# DC_Power_Regulation_-_Copy.net
KiCad netlist of a schematic drawn in Altium Designer
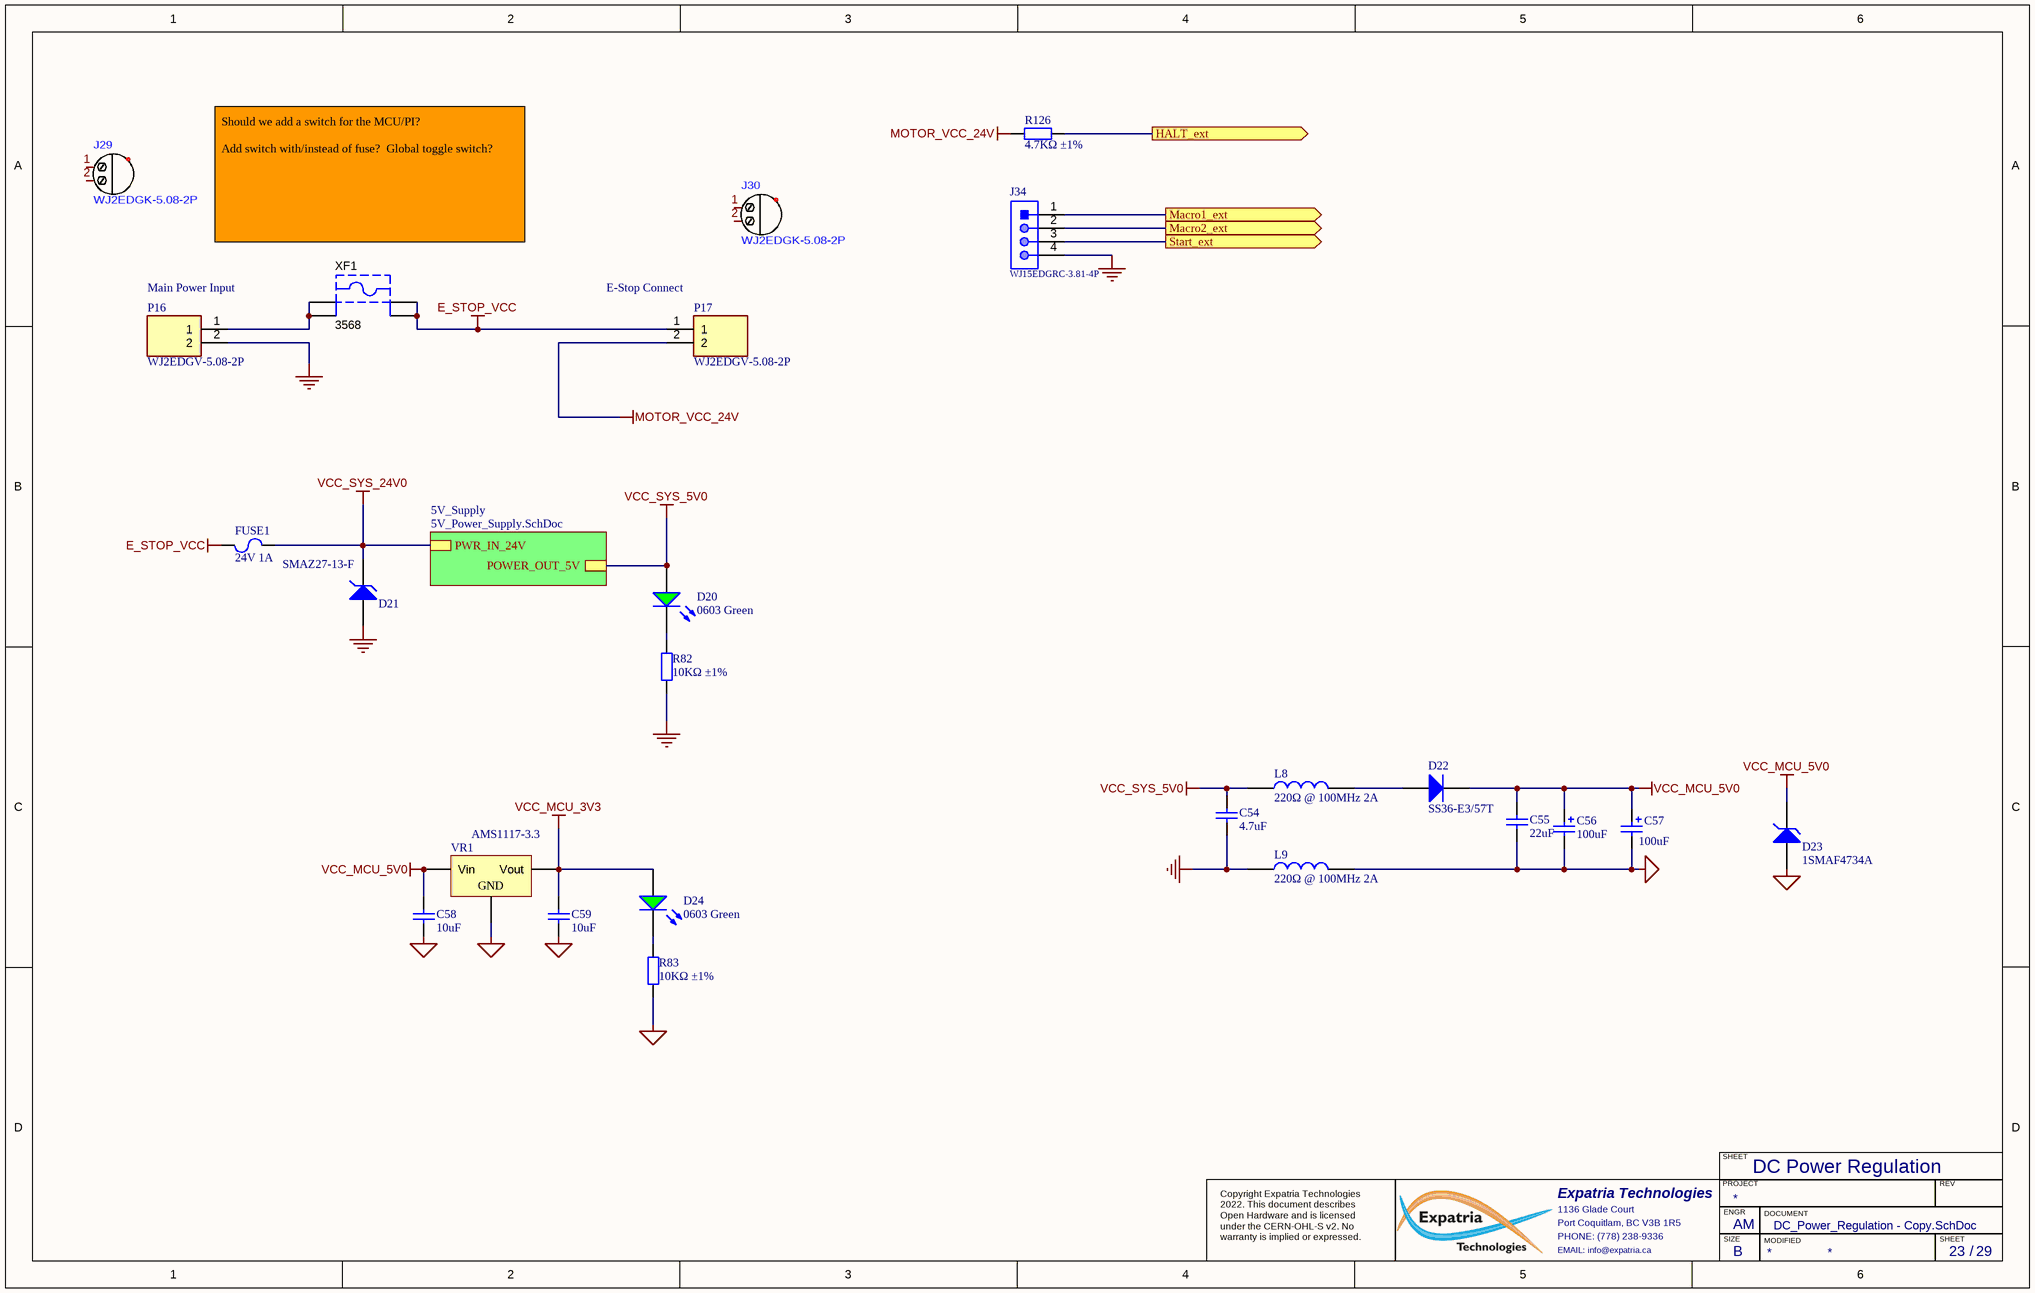
[diagram p0: DC_Power_Regulation - Copy.SchDoc]

(export (version "E")
  (design (tool "Eeschema 10.0.6"))
  (components
    (comp (ref "C54")
      (value "4.7uF")
      (footprint "0603_C")
      (description "Chip capacitors")
      (fields
        (field (name "MANUFACTURER") "Samsung Electro-Mechanics")
        (field (name "PARTNUMBER") "CL10A475KO8NNNC")
      )
      (libsource (lib "Cap") (part "0603 4.7uF (475) 10% 16V"))
    )
    (comp (ref "C55")
      (value "22uF")
      (footprint "0805_C")
      (description "Chip capacitors")
      (fields
        (field (name "MANUFACTURER") "Samsung Electro-Mechanics")
        (field (name "PARTNUMBER") "CL21A226MAQNNNE")
      )
      (libsource (lib "Cap") (part "0805 22uF (226) 20% 25V"))
    )
    (comp (ref "C56")
      (value "100uF")
      (footprint "CASE-B_3528")
      (description "Tantalum capacitor")
      (fields (field (name "MANUFACTURER") "AVX") (field (name "PARTNUMBER") "TAJB107K006RNJ"))
      (libsource (lib "Cap") (part "3528 100uF (107) 10% 6.3V"))
    )
    (comp (ref "C57")
      (value "100uF")
      (footprint "WCAP-ASLI_D6.3H7.7")
      (fields (field (name "MANUFACTURER") "Capxon International Elec"))
      (libsource (lib "IQAnalog") (part "865080445010"))
    )
    (comp (ref "C58")
      (value "10uF")
      (footprint "1206_C")
      (description "Chip capacitors")
      (fields
        (field (name "MANUFACTURER") "Samsung Electro-Mechanics")
        (field (name "PARTNUMBER") "CL31A106KBHNNNE")
      )
      (libsource (lib "Cap") (part "1206 10uF (106) 10% 50V"))
    )
    (comp (ref "C59")
      (value "10uF")
      (footprint "1206_C")
      (description "Chip capacitors")
      (fields
        (field (name "MANUFACTURER") "Samsung Electro-Mechanics")
        (field (name "PARTNUMBER") "CL31A106KBHNNNE")
      )
      (libsource (lib "Cap") (part "1206 10uF (106) 10% 50V"))
    )
    (comp (ref "D20")
      (value "0603 Green")
      (footprint "0603_LED_S1")
      (description "LED")
      (libsource (lib "LED") (part "0603 LED Green"))
    )
    (comp (ref "D21")
      (value "SMAZ27-13-F")
      (footprint "DIOM5226X240N")
      (description "27V ±5% 1W 500nA @ 20.5V SMA(DO-214AC) Zener Diodes RoHS")
      (libsource (lib "PrintNC_GRBLHAL_Breakout") (part "BZT52C27"))
    )
    (comp (ref "D22")
      (value "SS36-E3/57T")
      (footprint "SMC(DO-214AB)_S1")
      (description "DIODE SCHOTTKY 60V 3A DO214AB")
      (libsource (lib "Diode") (part "SMC(DO-214AB) SS36-E3/57T"))
    )
    (comp (ref "D23")
      (value "1SMAF4734A")
      (footprint "DIOM5226X240N")
      (description "27V ±5% 1W 500nA @ 20.5V SMA(DO-214AC) Zener Diodes RoHS")
      (libsource (lib "PrintNC_GRBLHAL_Breakout") (part "BZT52C27"))
    )
    (comp (ref "D24")
      (value "0603 Green")
      (footprint "0603_LED_S1")
      (description "LED")
      (libsource (lib "LED") (part "0603 LED Green"))
    )
    (comp (ref "FUSE1")
      (value "24V 1A")
      (footprint "1206_C")
      (description "24V 1A 0.1s 1206 PTC Resettable Fuses RoHS")
      (fields
        (field (name "MANUFACTURER") "Jinrui Electronic Materials Co.")
        (field (name "PARTNUMBER") "JK-nSMD050-24")
      )
      (libsource (lib "PrintNC_GRBLHAL_Breakout") (part "JK-nSMD050-24"))
    )
    (comp (ref "J29")
      (value "WJ2EDGK-5.08-2P")
      (description "5.08mm Green Plug P=5.08mm Pluggable System Terminal Block ROHS")
      (fields (field (name "MANUFACTURER") "Kangnex"))
      (libsource (lib "Sienci_Labs") (part "WJ2EDGK-5.08-2P"))
    )
    (comp (ref "J30")
      (value "WJ2EDGK-5.08-2P")
      (description "5.08mm Green Plug P=5.08mm Pluggable System Terminal Block ROHS")
      (fields (field (name "MANUFACTURER") "Kangnex"))
      (libsource (lib "Sienci_Labs") (part "WJ2EDGK-5.08-2P"))
    )
    (comp (ref "J34")
      (value "WJ15EDGRC-3.81-4P")
      (footprint "SHDRRA4W85P0X381_1X4_1612X915X720P")
      (description "3.81mm Green Board Edge/Receptacle-Close Push-Pull,P=3.81mm Pluggable System Terminal Block ROHS")
      (fields (field (name "MANUFACTURER") "Ningbo Kangnex Elec"))
      (libsource (lib "Sienci_Labs") (part "WJ15EDGRC-3.81-4P"))
    )
    (comp (ref "L8")
      (value "220Ω @ 100MHz 2A")
      (footprint "0805_C")
      (description "220Ω @ 100MHz 2A 150mΩ 0805 Ferrite Beads ROHS")
      (libsource (lib "FBEAD") (part "0402 220R@100Mhz 0.1A"))
    )
    (comp (ref "L9")
      (value "220Ω @ 100MHz 2A")
      (footprint "0805_C")
      (description "220Ω @ 100MHz 1 2A 150mΩ 0805 Ferrite Beads ROHS")
      (libsource (lib "FBEAD") (part "0402 220R@100Mhz 0.1A"))
    )
    (comp (ref "P16")
      (value "WJ2EDGV-5.08-2P")
      (footprint "WJ2EDGV5082P")
      (description "5.08mm Green Board Edge/Receptacle-Open Straight,P=5.08mm Pluggable System Terminal Block ROHS")
      (fields (field (name "MANUFACTURER") "Kangnex"))
      (libsource (lib "Sienci_Labs") (part "WJ2EDGV-5.08-2P"))
    )
    (comp (ref "P17")
      (value "WJ2EDGV-5.08-2P")
      (footprint "WJ2EDGV5082P")
      (description "5.08mm Green Board Edge/Receptacle-Open Straight,P=5.08mm Pluggable System Terminal Block ROHS")
      (fields (field (name "MANUFACTURER") "Kangnex"))
      (libsource (lib "") (part "WJ2EDGV-5.08-2P_1"))
    )
    (comp (ref "R82")
      (value "10KΩ ±1%")
      (footprint "0603_R")
      (description "Chip resistor")
      (fields (field (name "MANUFACTURER") "Uniroyal Elec") (field (name "PARTNUMBER") "0603WAF1002T5E"))
      (libsource (lib "RES") (part "0603 10K (1002) 1%"))
    )
    (comp (ref "R83")
      (value "10KΩ ±1%")
      (footprint "0603_R")
      (description "Chip resistor")
      (fields (field (name "MANUFACTURER") "Uniroyal Elec") (field (name "PARTNUMBER") "0603WAF1002T5E"))
      (libsource (lib "RES") (part "0603 10K (1002) 1%"))
    )
    (comp (ref "R126")
      (value "4.7KΩ ±1%")
      (footprint "0603_R")
      (description "Chip resistor")
      (fields (field (name "MANUFACTURER") "Uniroyal Elec") (field (name "PARTNUMBER") "0603WAF4701T5E"))
      (libsource (lib "Sienci_Labs") (part "0603 4.7K (4701) 1%"))
    )
    (comp (ref "VR1")
      (value "AMS1117-3.3")
      (footprint "SOT-223")
      (description "Vout=3.3V 1A 72dB@(120Hz) (LDO)")
      (fields (field (name "MANUFACTURER") "AMS"))
      (libsource (lib "LDO") (part "SOT-223 AMS1117-3.3"))
    )
    (comp (ref "XF1")
      (value "3568")
      (footprint "KSTN-3568_V")
      (description "Fuse Holder, 20 A, 500 V, -50 to 145 degC, 4-Pin THD, RoHS")
      (fields
        (field (name "MANUFACTURER") "Keystone Electronics")
        (field (name "MANUFACTURER PART NUMBER") "3568-20")
      )
      (libsource (lib "Sienci_Labs") (part "3568-20"))
    )
  )
  (nets
    (net (code "1") (name "/HALT_ext") (class "Default")
      (node (ref "R126") (pin "1") (pinfunction "1_1") (pintype "passive"))
    )
    (net (code "2") (name "/Macro1_ext") (class "Default")
      (node (ref "J34") (pin "1") (pinfunction "1_1") (pintype "passive"))
    )
    (net (code "3") (name "/Macro2_ext") (class "Default")
      (node (ref "J34") (pin "2") (pinfunction "2_2") (pintype "passive"))
    )
    (net (code "4") (name "/Start_ext") (class "Default")
      (node (ref "J34") (pin "3") (pinfunction "3_3") (pintype "passive"))
    )
    (net (code "5") (name "E_STOP_VCC") (class "Default")
      (node (ref "FUSE1") (pin "1") (pinfunction "1_1") (pintype "passive"))
      (node (ref "P17") (pin "1") (pinfunction "1_1") (pintype "passive"))
      (node (ref "XF1") (pin "3") (pinfunction "3_3") (pintype "passive"))
      (node (ref "XF1") (pin "4") (pinfunction "4_4") (pintype "passive"))
    )
    (net (code "6") (name "GND") (class "Default")
      (node (ref "C54") (pin "1") (pinfunction "1_1") (pintype "passive"))
      (node (ref "D21") (pin "1") (pinfunction "A_1") (pintype "passive"))
      (node (ref "J34") (pin "4") (pinfunction "4_4") (pintype "passive"))
      (node (ref "L9") (pin "1") (pinfunction "1_1") (pintype "passive"))
      (node (ref "P16") (pin "2") (pinfunction "2_2") (pintype "passive"))
      (node (ref "R82") (pin "1") (pinfunction "1_1") (pintype "passive"))
    )
    (net (code "7") (name "MCU_GND") (class "Default")
      (node (ref "C55") (pin "1") (pinfunction "1_1") (pintype "passive"))
      (node (ref "C56") (pin "2") (pinfunction "2_2") (pintype "passive"))
      (node (ref "C57") (pin "2") (pinfunction "N_2") (pintype "passive"))
      (node (ref "C58") (pin "1") (pinfunction "1_1") (pintype "passive"))
      (node (ref "C59") (pin "1") (pinfunction "1_1") (pintype "passive"))
      (node (ref "D23") (pin "1") (pinfunction "A_1") (pintype "passive"))
      (node (ref "L9") (pin "2") (pinfunction "2_2") (pintype "passive"))
      (node (ref "R83") (pin "1") (pinfunction "1_1") (pintype "passive"))
      (node (ref "VR1") (pin "1") (pinfunction "GND_1") (pintype "passive"))
    )
    (net (code "8") (name "MOTOR_VCC_24V") (class "Default")
      (node (ref "P17") (pin "2") (pinfunction "2_2") (pintype "passive"))
      (node (ref "R126") (pin "2") (pinfunction "2_2") (pintype "passive"))
    )
    (net (code "9") (name "Net-(D20-PadK)") (class "Default")
      (node (ref "D20") (pin "K") (pinfunction "K_K") (pintype "passive"))
      (node (ref "R82") (pin "2") (pinfunction "2_2") (pintype "passive"))
    )
    (net (code "10") (name "Net-(D22-A)") (class "Default")
      (node (ref "D22") (pin "1") (pinfunction "A_1") (pintype "passive"))
      (node (ref "L8") (pin "2") (pinfunction "2_2") (pintype "passive"))
    )
    (net (code "11") (name "Net-(D24-PadK)") (class "Default")
      (node (ref "D24") (pin "K") (pinfunction "K_K") (pintype "passive"))
      (node (ref "R83") (pin "2") (pinfunction "2_2") (pintype "passive"))
    )
    (net (code "12") (name "Net-(P16-Pad1)") (class "Default")
      (node (ref "P16") (pin "1") (pinfunction "1_1") (pintype "passive"))
      (node (ref "XF1") (pin "1") (pinfunction "1_1") (pintype "passive"))
      (node (ref "XF1") (pin "2") (pinfunction "2_2") (pintype "passive"))
    )
    (net (code "13") (name "VCC_MCU_3V3") (class "Default")
      (node (ref "C59") (pin "2") (pinfunction "2_2") (pintype "passive"))
      (node (ref "D24") (pin "A") (pinfunction "A_A") (pintype "passive"))
      (node (ref "VR1") (pin "2") (pinfunction "Vout_2") (pintype "passive"))
    )
    (net (code "14") (name "VCC_MCU_5V0") (class "Default")
      (node (ref "C55") (pin "2") (pinfunction "2_2") (pintype "passive"))
      (node (ref "C56") (pin "1") (pinfunction "1_1") (pintype "passive"))
      (node (ref "C57") (pin "1") (pinfunction "P_1") (pintype "passive"))
      (node (ref "C58") (pin "2") (pinfunction "2_2") (pintype "passive"))
      (node (ref "D22") (pin "2") (pinfunction "K_2") (pintype "passive"))
      (node (ref "D23") (pin "2") (pinfunction "K_2") (pintype "passive"))
      (node (ref "VR1") (pin "3") (pinfunction "Vin_3") (pintype "passive"))
    )
    (net (code "15") (name "VCC_SYS_5V0") (class "Default")
      (node (ref "C54") (pin "2") (pinfunction "2_2") (pintype "passive"))
      (node (ref "D20") (pin "A") (pinfunction "A_A") (pintype "passive"))
      (node (ref "L8") (pin "1") (pinfunction "1_1") (pintype "passive"))
    )
    (net (code "16") (name "VCC_SYS_24V0") (class "Default")
      (node (ref "D21") (pin "2") (pinfunction "K_2") (pintype "passive"))
      (node (ref "FUSE1") (pin "2") (pinfunction "2_2") (pintype "passive"))
    )
    (net (code "17") (name "unconnected-(J29-Pad1)") (class "Default")
      (node (ref "J29") (pin "1") (pinfunction "1_1") (pintype "passive"))
    )
    (net (code "18") (name "unconnected-(J29-Pad2)") (class "Default")
      (node (ref "J29") (pin "2") (pinfunction "2_2") (pintype "passive"))
    )
    (net (code "19") (name "unconnected-(J30-Pad1)") (class "Default")
      (node (ref "J30") (pin "1") (pinfunction "1_1") (pintype "passive"))
    )
    (net (code "20") (name "unconnected-(J30-Pad2)") (class "Default")
      (node (ref "J30") (pin "2") (pinfunction "2_2") (pintype "passive"))
    )
  )
)
